# POWER_CONTROL.net
KiCad netlist of a schematic drawn in Altium Designer
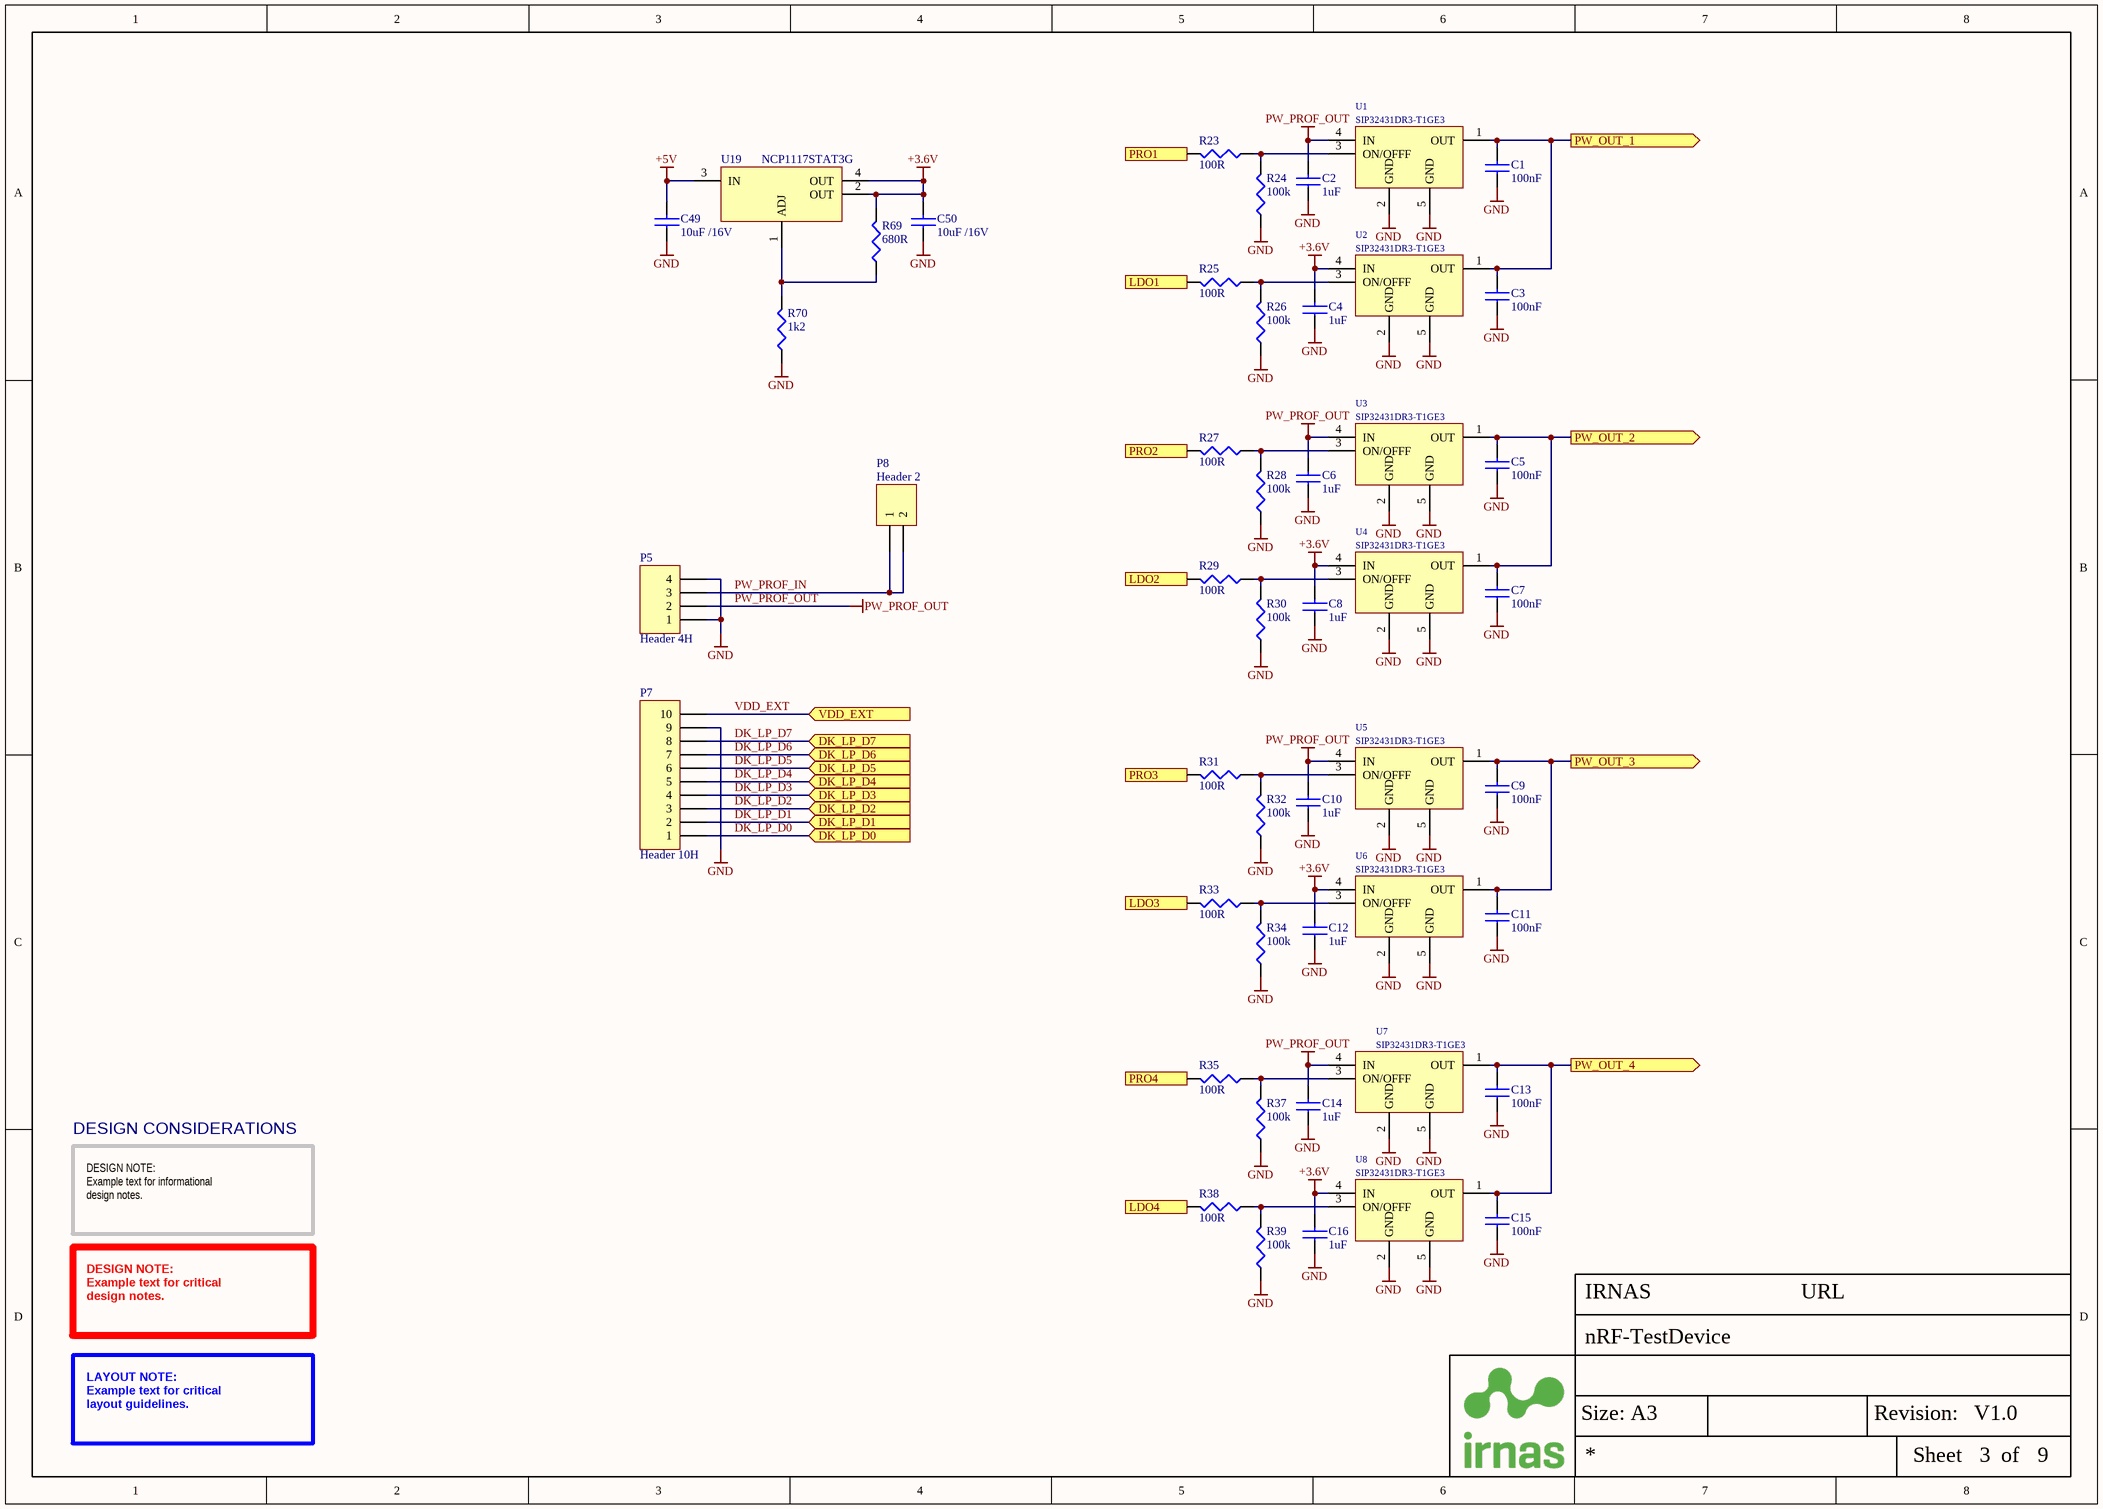
[diagram p0: POWER_CONTROL.SchDoc]

(export (version "E")
  (design (tool "Eeschema 10.0.6"))
  (components
    (comp (ref "C1")
      (value "100nF")
      (footprint "CAP0402")
      (fields
        (field (name "MANUFACTURER") "Multicomp")
        (field (name "MANUFACTURER PART NUMBER") "MC0402X104J160CT")
        (field (name "TOLERANCE") "5%")
      )
      (libsource (lib "Passive") (part "C - 100nF/0402"))
    )
    (comp (ref "C2")
      (value "1uF")
      (footprint "CAP0402")
      (description "CAP CER 1UF 10V 20% X5R 0402")
      (fields
        (field (name "MANUFACTURER") "Murata")
        (field (name "MANUFACTURER PART NUMBER") "GRM155R61A105ME15D")
      )
      (libsource (lib "Passive") (part "C - 1uF/0402"))
    )
    (comp (ref "C3")
      (value "100nF")
      (footprint "CAP0402")
      (fields
        (field (name "MANUFACTURER") "Multicomp")
        (field (name "MANUFACTURER PART NUMBER") "MC0402X104J160CT")
        (field (name "TOLERANCE") "5%")
      )
      (libsource (lib "Passive") (part "C - 100nF/0402"))
    )
    (comp (ref "C4")
      (value "1uF")
      (footprint "CAP0402")
      (description "CAP CER 1UF 10V 20% X5R 0402")
      (fields
        (field (name "MANUFACTURER") "Murata")
        (field (name "MANUFACTURER PART NUMBER") "GRM155R61A105ME15D")
      )
      (libsource (lib "Passive") (part "C - 1uF/0402"))
    )
    (comp (ref "C5")
      (value "100nF")
      (footprint "CAP0402")
      (fields
        (field (name "MANUFACTURER") "Multicomp")
        (field (name "MANUFACTURER PART NUMBER") "MC0402X104J160CT")
        (field (name "TOLERANCE") "5%")
      )
      (libsource (lib "Passive") (part "C - 100nF/0402"))
    )
    (comp (ref "C6")
      (value "1uF")
      (footprint "CAP0402")
      (description "CAP CER 1UF 10V 20% X5R 0402")
      (fields
        (field (name "MANUFACTURER") "Murata")
        (field (name "MANUFACTURER PART NUMBER") "GRM155R61A105ME15D")
      )
      (libsource (lib "Passive") (part "C - 1uF/0402"))
    )
    (comp (ref "C7")
      (value "100nF")
      (footprint "CAP0402")
      (fields
        (field (name "MANUFACTURER") "Multicomp")
        (field (name "MANUFACTURER PART NUMBER") "MC0402X104J160CT")
        (field (name "TOLERANCE") "5%")
      )
      (libsource (lib "Passive") (part "C - 100nF/0402"))
    )
    (comp (ref "C8")
      (value "1uF")
      (footprint "CAP0402")
      (description "CAP CER 1UF 10V 20% X5R 0402")
      (fields
        (field (name "MANUFACTURER") "Murata")
        (field (name "MANUFACTURER PART NUMBER") "GRM155R61A105ME15D")
      )
      (libsource (lib "Passive") (part "C - 1uF/0402"))
    )
    (comp (ref "C9")
      (value "100nF")
      (footprint "CAP0402")
      (fields
        (field (name "MANUFACTURER") "Multicomp")
        (field (name "MANUFACTURER PART NUMBER") "MC0402X104J160CT")
        (field (name "TOLERANCE") "5%")
      )
      (libsource (lib "Passive") (part "C - 100nF/0402"))
    )
    (comp (ref "C10")
      (value "1uF")
      (footprint "CAP0402")
      (description "CAP CER 1UF 10V 20% X5R 0402")
      (fields
        (field (name "MANUFACTURER") "Murata")
        (field (name "MANUFACTURER PART NUMBER") "GRM155R61A105ME15D")
      )
      (libsource (lib "Passive") (part "C - 1uF/0402"))
    )
    (comp (ref "C11")
      (value "100nF")
      (footprint "CAP0402")
      (fields
        (field (name "MANUFACTURER") "Multicomp")
        (field (name "MANUFACTURER PART NUMBER") "MC0402X104J160CT")
        (field (name "TOLERANCE") "5%")
      )
      (libsource (lib "Passive") (part "C - 100nF/0402"))
    )
    (comp (ref "C12")
      (value "1uF")
      (footprint "CAP0402")
      (description "CAP CER 1UF 10V 20% X5R 0402")
      (fields
        (field (name "MANUFACTURER") "Murata")
        (field (name "MANUFACTURER PART NUMBER") "GRM155R61A105ME15D")
      )
      (libsource (lib "Passive") (part "C - 1uF/0402"))
    )
    (comp (ref "C13")
      (value "100nF")
      (footprint "CAP0402")
      (fields
        (field (name "MANUFACTURER") "Multicomp")
        (field (name "MANUFACTURER PART NUMBER") "MC0402X104J160CT")
        (field (name "TOLERANCE") "5%")
      )
      (libsource (lib "Passive") (part "C - 100nF/0402"))
    )
    (comp (ref "C14")
      (value "1uF")
      (footprint "CAP0402")
      (description "CAP CER 1UF 10V 20% X5R 0402")
      (fields
        (field (name "MANUFACTURER") "Murata")
        (field (name "MANUFACTURER PART NUMBER") "GRM155R61A105ME15D")
      )
      (libsource (lib "Passive") (part "C - 1uF/0402"))
    )
    (comp (ref "C15")
      (value "100nF")
      (footprint "CAP0402")
      (fields
        (field (name "MANUFACTURER") "Multicomp")
        (field (name "MANUFACTURER PART NUMBER") "MC0402X104J160CT")
        (field (name "TOLERANCE") "5%")
      )
      (libsource (lib "Passive") (part "C - 100nF/0402"))
    )
    (comp (ref "C16")
      (value "1uF")
      (footprint "CAP0402")
      (description "CAP CER 1UF 10V 20% X5R 0402")
      (fields
        (field (name "MANUFACTURER") "Murata")
        (field (name "MANUFACTURER PART NUMBER") "GRM155R61A105ME15D")
      )
      (libsource (lib "Passive") (part "C - 1uF/0402"))
    )
    (comp (ref "C49")
      (value "10uF /16V")
      (footprint "CAP0805")
      (description "TDK - CGA4J1X5R1C106K125AC - CAP, MLCC, X5R, 10UF, 16V, 0805")
      (fields
        (field (name "MANUFACTURER") "TDK")
        (field (name "MANUFACTURER PART NUMBER") "CGA4J1X5R1C106K125AC")
      )
      (libsource (lib "Passive") (part "C - 10uF /16V"))
    )
    (comp (ref "C50")
      (value "10uF /16V")
      (footprint "CAP0805")
      (description "TDK - CGA4J1X5R1C106K125AC - CAP, MLCC, X5R, 10UF, 16V, 0805")
      (fields
        (field (name "MANUFACTURER") "TDK")
        (field (name "MANUFACTURER PART NUMBER") "CGA4J1X5R1C106K125AC")
      )
      (libsource (lib "Passive") (part "C - 10uF /16V"))
    )
    (comp (ref "P5")
      (value "Header 4H")
      (footprint "HDR1X4H")
      (description "Header, 4-Pin, Right Angle")
      (fields (field (name "PUBLISHER") "Altium Limited"))
      (libsource (lib "Miscellaneous Connectors") (part "Header 4H"))
    )
    (comp (ref "P7")
      (value "Header 10H")
      (footprint "HDR1X10H")
      (description "Header, 10-Pin, Right Angle")
      (fields (field (name "PUBLISHER") "Altium Limited"))
      (libsource (lib "Miscellaneous Connectors") (part "Header 10H"))
    )
    (comp (ref "P8")
      (value "Header 2")
      (footprint "HDR1X2")
      (description "Header, 2-Pin")
      (fields (field (name "PUBLISHER") "Altium Limited"))
      (libsource (lib "Miscellaneous Connectors") (part "Header 2"))
    )
    (comp (ref "R23")
      (value "100R")
      (footprint "RES0402")
      (fields
        (field (name "MANUFACTURER") "Multicomp")
        (field (name "MANUFACTURER PART NUMBER") "MCMR04X1000FTL")
        (field (name "TOLERANCE") "1%")
      )
      (libsource (lib "Passive") (part "R - 100R/0402"))
    )
    (comp (ref "R24")
      (value "100k")
      (footprint "RES0402")
      (description "MULTICOMP   MCWR04X1003FTL   RES, THICK FILM, 100KOHM, 1%, 0.0625W")
      (fields
        (field (name "MANUFACTURER") "Multicomp")
        (field (name "MANUFACTURER PART NUMBER") "MCWR04X1003FTL")
      )
      (libsource (lib "Passive") (part "R - 100k/0402"))
    )
    (comp (ref "R25")
      (value "100R")
      (footprint "RES0402")
      (fields
        (field (name "MANUFACTURER") "Multicomp")
        (field (name "MANUFACTURER PART NUMBER") "MCMR04X1000FTL")
        (field (name "TOLERANCE") "1%")
      )
      (libsource (lib "Passive") (part "R - 100R/0402"))
    )
    (comp (ref "R26")
      (value "100k")
      (footprint "RES0402")
      (description "MULTICOMP   MCWR04X1003FTL   RES, THICK FILM, 100KOHM, 1%, 0.0625W")
      (fields
        (field (name "MANUFACTURER") "Multicomp")
        (field (name "MANUFACTURER PART NUMBER") "MCWR04X1003FTL")
      )
      (libsource (lib "Passive") (part "R - 100k/0402"))
    )
    (comp (ref "R27")
      (value "100R")
      (footprint "RES0402")
      (fields
        (field (name "MANUFACTURER") "Multicomp")
        (field (name "MANUFACTURER PART NUMBER") "MCMR04X1000FTL")
        (field (name "TOLERANCE") "1%")
      )
      (libsource (lib "Passive") (part "R - 100R/0402"))
    )
    (comp (ref "R28")
      (value "100k")
      (footprint "RES0402")
      (description "MULTICOMP   MCWR04X1003FTL   RES, THICK FILM, 100KOHM, 1%, 0.0625W")
      (fields
        (field (name "MANUFACTURER") "Multicomp")
        (field (name "MANUFACTURER PART NUMBER") "MCWR04X1003FTL")
      )
      (libsource (lib "Passive") (part "R - 100k/0402"))
    )
    (comp (ref "R29")
      (value "100R")
      (footprint "RES0402")
      (fields
        (field (name "MANUFACTURER") "Multicomp")
        (field (name "MANUFACTURER PART NUMBER") "MCMR04X1000FTL")
        (field (name "TOLERANCE") "1%")
      )
      (libsource (lib "Passive") (part "R - 100R/0402"))
    )
    (comp (ref "R30")
      (value "100k")
      (footprint "RES0402")
      (description "MULTICOMP   MCWR04X1003FTL   RES, THICK FILM, 100KOHM, 1%, 0.0625W")
      (fields
        (field (name "MANUFACTURER") "Multicomp")
        (field (name "MANUFACTURER PART NUMBER") "MCWR04X1003FTL")
      )
      (libsource (lib "Passive") (part "R - 100k/0402"))
    )
    (comp (ref "R31")
      (value "100R")
      (footprint "RES0402")
      (fields
        (field (name "MANUFACTURER") "Multicomp")
        (field (name "MANUFACTURER PART NUMBER") "MCMR04X1000FTL")
        (field (name "TOLERANCE") "1%")
      )
      (libsource (lib "Passive") (part "R - 100R/0402"))
    )
    (comp (ref "R32")
      (value "100k")
      (footprint "RES0402")
      (description "MULTICOMP   MCWR04X1003FTL   RES, THICK FILM, 100KOHM, 1%, 0.0625W")
      (fields
        (field (name "MANUFACTURER") "Multicomp")
        (field (name "MANUFACTURER PART NUMBER") "MCWR04X1003FTL")
      )
      (libsource (lib "Passive") (part "R - 100k/0402"))
    )
    (comp (ref "R33")
      (value "100R")
      (footprint "RES0402")
      (fields
        (field (name "MANUFACTURER") "Multicomp")
        (field (name "MANUFACTURER PART NUMBER") "MCMR04X1000FTL")
        (field (name "TOLERANCE") "1%")
      )
      (libsource (lib "Passive") (part "R - 100R/0402"))
    )
    (comp (ref "R34")
      (value "100k")
      (footprint "RES0402")
      (description "MULTICOMP   MCWR04X1003FTL   RES, THICK FILM, 100KOHM, 1%, 0.0625W")
      (fields
        (field (name "MANUFACTURER") "Multicomp")
        (field (name "MANUFACTURER PART NUMBER") "MCWR04X1003FTL")
      )
      (libsource (lib "Passive") (part "R - 100k/0402"))
    )
    (comp (ref "R35")
      (value "100R")
      (footprint "RES0402")
      (fields
        (field (name "MANUFACTURER") "Multicomp")
        (field (name "MANUFACTURER PART NUMBER") "MCMR04X1000FTL")
        (field (name "TOLERANCE") "1%")
      )
      (libsource (lib "Passive") (part "R - 100R/0402"))
    )
    (comp (ref "R37")
      (value "100k")
      (footprint "RES0402")
      (description "MULTICOMP   MCWR04X1003FTL   RES, THICK FILM, 100KOHM, 1%, 0.0625W")
      (fields
        (field (name "MANUFACTURER") "Multicomp")
        (field (name "MANUFACTURER PART NUMBER") "MCWR04X1003FTL")
      )
      (libsource (lib "Passive") (part "R - 100k/0402"))
    )
    (comp (ref "R38")
      (value "100R")
      (footprint "RES0402")
      (fields
        (field (name "MANUFACTURER") "Multicomp")
        (field (name "MANUFACTURER PART NUMBER") "MCMR04X1000FTL")
        (field (name "TOLERANCE") "1%")
      )
      (libsource (lib "Passive") (part "R - 100R/0402"))
    )
    (comp (ref "R39")
      (value "100k")
      (footprint "RES0402")
      (description "MULTICOMP   MCWR04X1003FTL   RES, THICK FILM, 100KOHM, 1%, 0.0625W")
      (fields
        (field (name "MANUFACTURER") "Multicomp")
        (field (name "MANUFACTURER PART NUMBER") "MCWR04X1003FTL")
      )
      (libsource (lib "Passive") (part "R - 100k/0402"))
    )
    (comp (ref "R69")
      (value "680R")
      (footprint "RES0402")
      (description "RES 680 ohm, ± 1%, 63 mW, 0402")
      (fields
        (field (name "MANUFACTURER") "Vishay")
        (field (name "MANUFACTURER PART NUMBER") "CRCW0402680RFKED")
      )
      (libsource (lib "Passive") (part "R - 680R/0402"))
    )
    (comp (ref "R70")
      (value "1k2")
      (footprint "RES0402")
      (description "RES SMD 1.2K OHM 1% 1/16W 0402")
      (fields
        (field (name "MANUFACTURER") "Vishay")
        (field (name "MANUFACTURER PART NUMBER") "CRCW04021K20FKED")
      )
      (libsource (lib "Passive") (part "R - 1k2/0402"))
    )
    (comp (ref "U1")
      (value "SIP32431DR3-T1GE3")
      (footprint "SC70-6")
      (description "Power Load Switch, Reverse Blocking, High Side, Active High, Active Low, 1 Output, 5.5V, 1A")
      (libsource (lib "Active") (part "SW - SIP32431DR3-T1GE3"))
    )
    (comp (ref "U2")
      (value "SIP32431DR3-T1GE3")
      (footprint "SC70-6")
      (description "Power Load Switch, Reverse Blocking, High Side, Active High, Active Low, 1 Output, 5.5V, 1A")
      (libsource (lib "Active") (part "SW - SIP32431DR3-T1GE3"))
    )
    (comp (ref "U3")
      (value "SIP32431DR3-T1GE3")
      (footprint "SC70-6")
      (description "Power Load Switch, Reverse Blocking, High Side, Active High, Active Low, 1 Output, 5.5V, 1A")
      (libsource (lib "Active") (part "SW - SIP32431DR3-T1GE3"))
    )
    (comp (ref "U4")
      (value "SIP32431DR3-T1GE3")
      (footprint "SC70-6")
      (description "Power Load Switch, Reverse Blocking, High Side, Active High, Active Low, 1 Output, 5.5V, 1A")
      (libsource (lib "Active") (part "SW - SIP32431DR3-T1GE3"))
    )
    (comp (ref "U5")
      (value "SIP32431DR3-T1GE3")
      (footprint "SC70-6")
      (description "Power Load Switch, Reverse Blocking, High Side, Active High, Active Low, 1 Output, 5.5V, 1A")
      (libsource (lib "Active") (part "SW - SIP32431DR3-T1GE3"))
    )
    (comp (ref "U6")
      (value "SIP32431DR3-T1GE3")
      (footprint "SC70-6")
      (description "Power Load Switch, Reverse Blocking, High Side, Active High, Active Low, 1 Output, 5.5V, 1A")
      (libsource (lib "Active") (part "SW - SIP32431DR3-T1GE3"))
    )
    (comp (ref "U7")
      (value "SIP32431DR3-T1GE3")
      (footprint "SC70-6")
      (description "Power Load Switch, Reverse Blocking, High Side, Active High, Active Low, 1 Output, 5.5V, 1A")
      (libsource (lib "Active") (part "SW - SIP32431DR3-T1GE3"))
    )
    (comp (ref "U8")
      (value "SIP32431DR3-T1GE3")
      (footprint "SC70-6")
      (description "Power Load Switch, Reverse Blocking, High Side, Active High, Active Low, 1 Output, 5.5V, 1A")
      (libsource (lib "Active") (part "SW - SIP32431DR3-T1GE3"))
    )
    (comp (ref "U19")
      (value "NCP1117STAT3G")
      (footprint "SOT223-3")
      (description "LDO Voltage Regulator, Adjustable, 3.5V to 20V in, 1.07V drop, 1.25V to 18.8V/1A out, SOT-223-3")
      (fields (field (name "MANUFACTURER") "ON SEMICONDUCTOR"))
      (libsource (lib "Active") (part "V_LIN - NCP1117STAT3G"))
    )
  )
  (nets
    (net (code "1") (name "+3.6V") (class "Default")
      (node (ref "C12") (pin "2") (pinfunction "2_2") (pintype "passive"))
      (node (ref "C16") (pin "2") (pinfunction "2_2") (pintype "passive"))
      (node (ref "C4") (pin "2") (pinfunction "2_2") (pintype "passive"))
      (node (ref "C50") (pin "2") (pinfunction "2_2") (pintype "passive"))
      (node (ref "C8") (pin "2") (pinfunction "2_2") (pintype "passive"))
      (node (ref "R69") (pin "2") (pinfunction "2_2") (pintype "passive"))
      (node (ref "U19") (pin "2") (pinfunction "OUT_2") (pintype "open_collector"))
      (node (ref "U19") (pin "4") (pinfunction "OUT_4") (pintype "open_collector"))
      (node (ref "U2") (pin "4") (pinfunction "IN_4") (pintype "passive"))
      (node (ref "U4") (pin "4") (pinfunction "IN_4") (pintype "passive"))
      (node (ref "U6") (pin "4") (pinfunction "IN_4") (pintype "passive"))
      (node (ref "U8") (pin "4") (pinfunction "IN_4") (pintype "passive"))
    )
    (net (code "2") (name "+5V") (class "Default")
      (node (ref "C49") (pin "2") (pinfunction "2_2") (pintype "passive"))
      (node (ref "U19") (pin "3") (pinfunction "IN_3") (pintype "open_collector"))
    )
    (net (code "3") (name "/DK_LP_D0") (class "Default")
      (node (ref "P7") (pin "1") (pinfunction "1_1") (pintype "passive"))
    )
    (net (code "4") (name "/DK_LP_D1") (class "Default")
      (node (ref "P7") (pin "2") (pinfunction "2_2") (pintype "passive"))
    )
    (net (code "5") (name "/DK_LP_D2") (class "Default")
      (node (ref "P7") (pin "3") (pinfunction "3_3") (pintype "passive"))
    )
    (net (code "6") (name "/DK_LP_D3") (class "Default")
      (node (ref "P7") (pin "4") (pinfunction "4_4") (pintype "passive"))
    )
    (net (code "7") (name "/DK_LP_D4") (class "Default")
      (node (ref "P7") (pin "5") (pinfunction "5_5") (pintype "passive"))
    )
    (net (code "8") (name "/DK_LP_D5") (class "Default")
      (node (ref "P7") (pin "6") (pinfunction "6_6") (pintype "passive"))
    )
    (net (code "9") (name "/DK_LP_D6") (class "Default")
      (node (ref "P7") (pin "7") (pinfunction "7_7") (pintype "passive"))
    )
    (net (code "10") (name "/DK_LP_D7") (class "Default")
      (node (ref "P7") (pin "8") (pinfunction "8_8") (pintype "passive"))
    )
    (net (code "11") (name "/LDO1") (class "Default")
      (node (ref "R25") (pin "2") (pinfunction "2_2") (pintype "passive"))
    )
    (net (code "12") (name "/LDO2") (class "Default")
      (node (ref "R29") (pin "2") (pinfunction "2_2") (pintype "passive"))
    )
    (net (code "13") (name "/LDO3") (class "Default")
      (node (ref "R33") (pin "2") (pinfunction "2_2") (pintype "passive"))
    )
    (net (code "14") (name "/LDO4") (class "Default")
      (node (ref "R38") (pin "2") (pinfunction "2_2") (pintype "passive"))
    )
    (net (code "15") (name "/PRO1") (class "Default")
      (node (ref "R23") (pin "2") (pinfunction "2_2") (pintype "passive"))
    )
    (net (code "16") (name "/PRO2") (class "Default")
      (node (ref "R27") (pin "2") (pinfunction "2_2") (pintype "passive"))
    )
    (net (code "17") (name "/PRO3") (class "Default")
      (node (ref "R31") (pin "2") (pinfunction "2_2") (pintype "passive"))
    )
    (net (code "18") (name "/PRO4") (class "Default")
      (node (ref "R35") (pin "2") (pinfunction "2_2") (pintype "passive"))
    )
    (net (code "19") (name "/PW_OUT_1") (class "Default")
      (node (ref "C1") (pin "2") (pinfunction "2_2") (pintype "passive"))
      (node (ref "C3") (pin "2") (pinfunction "2_2") (pintype "passive"))
      (node (ref "U1") (pin "1") (pinfunction "OUT_1") (pintype "passive"))
      (node (ref "U2") (pin "1") (pinfunction "OUT_1") (pintype "passive"))
    )
    (net (code "20") (name "/PW_OUT_2") (class "Default")
      (node (ref "C5") (pin "2") (pinfunction "2_2") (pintype "passive"))
      (node (ref "C7") (pin "2") (pinfunction "2_2") (pintype "passive"))
      (node (ref "U3") (pin "1") (pinfunction "OUT_1") (pintype "passive"))
      (node (ref "U4") (pin "1") (pinfunction "OUT_1") (pintype "passive"))
    )
    (net (code "21") (name "/PW_OUT_3") (class "Default")
      (node (ref "C11") (pin "2") (pinfunction "2_2") (pintype "passive"))
      (node (ref "C9") (pin "2") (pinfunction "2_2") (pintype "passive"))
      (node (ref "U5") (pin "1") (pinfunction "OUT_1") (pintype "passive"))
      (node (ref "U6") (pin "1") (pinfunction "OUT_1") (pintype "passive"))
    )
    (net (code "22") (name "/PW_OUT_4") (class "Default")
      (node (ref "C13") (pin "2") (pinfunction "2_2") (pintype "passive"))
      (node (ref "C15") (pin "2") (pinfunction "2_2") (pintype "passive"))
      (node (ref "U7") (pin "1") (pinfunction "OUT_1") (pintype "passive"))
      (node (ref "U8") (pin "1") (pinfunction "OUT_1") (pintype "passive"))
    )
    (net (code "23") (name "/PW_PROF_IN") (class "Default")
      (node (ref "P5") (pin "3") (pinfunction "3_3") (pintype "passive"))
      (node (ref "P8") (pin "1") (pinfunction "1_1") (pintype "passive"))
      (node (ref "P8") (pin "2") (pinfunction "2_2") (pintype "passive"))
    )
    (net (code "24") (name "/VDD_EXT") (class "Default")
      (node (ref "P7") (pin "10") (pinfunction "10_10") (pintype "passive"))
    )
    (net (code "25") (name "GND") (class "Default")
      (node (ref "C1") (pin "1") (pinfunction "1_1") (pintype "passive"))
      (node (ref "C10") (pin "1") (pinfunction "1_1") (pintype "passive"))
      (node (ref "C11") (pin "1") (pinfunction "1_1") (pintype "passive"))
      (node (ref "C12") (pin "1") (pinfunction "1_1") (pintype "passive"))
      (node (ref "C13") (pin "1") (pinfunction "1_1") (pintype "passive"))
      (node (ref "C14") (pin "1") (pinfunction "1_1") (pintype "passive"))
      (node (ref "C15") (pin "1") (pinfunction "1_1") (pintype "passive"))
      (node (ref "C16") (pin "1") (pinfunction "1_1") (pintype "passive"))
      (node (ref "C2") (pin "1") (pinfunction "1_1") (pintype "passive"))
      (node (ref "C3") (pin "1") (pinfunction "1_1") (pintype "passive"))
      (node (ref "C4") (pin "1") (pinfunction "1_1") (pintype "passive"))
      (node (ref "C49") (pin "1") (pinfunction "1_1") (pintype "passive"))
      (node (ref "C5") (pin "1") (pinfunction "1_1") (pintype "passive"))
      (node (ref "C50") (pin "1") (pinfunction "1_1") (pintype "passive"))
      (node (ref "C6") (pin "1") (pinfunction "1_1") (pintype "passive"))
      (node (ref "C7") (pin "1") (pinfunction "1_1") (pintype "passive"))
      (node (ref "C8") (pin "1") (pinfunction "1_1") (pintype "passive"))
      (node (ref "C9") (pin "1") (pinfunction "1_1") (pintype "passive"))
      (node (ref "P5") (pin "1") (pinfunction "1_1") (pintype "passive"))
      (node (ref "P5") (pin "4") (pinfunction "4_4") (pintype "passive"))
      (node (ref "P7") (pin "9") (pinfunction "9_9") (pintype "passive"))
      (node (ref "R24") (pin "1") (pinfunction "1_1") (pintype "passive"))
      (node (ref "R26") (pin "1") (pinfunction "1_1") (pintype "passive"))
      (node (ref "R28") (pin "1") (pinfunction "1_1") (pintype "passive"))
      (node (ref "R30") (pin "1") (pinfunction "1_1") (pintype "passive"))
      (node (ref "R32") (pin "1") (pinfunction "1_1") (pintype "passive"))
      (node (ref "R34") (pin "1") (pinfunction "1_1") (pintype "passive"))
      (node (ref "R37") (pin "1") (pinfunction "1_1") (pintype "passive"))
      (node (ref "R39") (pin "1") (pinfunction "1_1") (pintype "passive"))
      (node (ref "R70") (pin "1") (pinfunction "1_1") (pintype "passive"))
      (node (ref "U1") (pin "2") (pinfunction "GND_2") (pintype "passive"))
      (node (ref "U1") (pin "5") (pinfunction "GND_5") (pintype "passive"))
      (node (ref "U2") (pin "2") (pinfunction "GND_2") (pintype "passive"))
      (node (ref "U2") (pin "5") (pinfunction "GND_5") (pintype "passive"))
      (node (ref "U3") (pin "2") (pinfunction "GND_2") (pintype "passive"))
      (node (ref "U3") (pin "5") (pinfunction "GND_5") (pintype "passive"))
      (node (ref "U4") (pin "2") (pinfunction "GND_2") (pintype "passive"))
      (node (ref "U4") (pin "5") (pinfunction "GND_5") (pintype "passive"))
      (node (ref "U5") (pin "2") (pinfunction "GND_2") (pintype "passive"))
      (node (ref "U5") (pin "5") (pinfunction "GND_5") (pintype "passive"))
      (node (ref "U6") (pin "2") (pinfunction "GND_2") (pintype "passive"))
      (node (ref "U6") (pin "5") (pinfunction "GND_5") (pintype "passive"))
      (node (ref "U7") (pin "2") (pinfunction "GND_2") (pintype "passive"))
      (node (ref "U7") (pin "5") (pinfunction "GND_5") (pintype "passive"))
      (node (ref "U8") (pin "2") (pinfunction "GND_2") (pintype "passive"))
      (node (ref "U8") (pin "5") (pinfunction "GND_5") (pintype "passive"))
    )
    (net (code "26") (name "Net-(U1-ON{slash}OFFF)") (class "Default")
      (node (ref "R23") (pin "1") (pinfunction "1_1") (pintype "passive"))
      (node (ref "R24") (pin "2") (pinfunction "2_2") (pintype "passive"))
      (node (ref "U1") (pin "3") (pinfunction "ON/OFFF_3") (pintype "passive"))
    )
    (net (code "27") (name "Net-(U2-ON{slash}OFFF)") (class "Default")
      (node (ref "R25") (pin "1") (pinfunction "1_1") (pintype "passive"))
      (node (ref "R26") (pin "2") (pinfunction "2_2") (pintype "passive"))
      (node (ref "U2") (pin "3") (pinfunction "ON/OFFF_3") (pintype "passive"))
    )
    (net (code "28") (name "Net-(U3-ON{slash}OFFF)") (class "Default")
      (node (ref "R27") (pin "1") (pinfunction "1_1") (pintype "passive"))
      (node (ref "R28") (pin "2") (pinfunction "2_2") (pintype "passive"))
      (node (ref "U3") (pin "3") (pinfunction "ON/OFFF_3") (pintype "passive"))
    )
    (net (code "29") (name "Net-(U4-ON{slash}OFFF)") (class "Default")
      (node (ref "R29") (pin "1") (pinfunction "1_1") (pintype "passive"))
      (node (ref "R30") (pin "2") (pinfunction "2_2") (pintype "passive"))
      (node (ref "U4") (pin "3") (pinfunction "ON/OFFF_3") (pintype "passive"))
    )
    (net (code "30") (name "Net-(U5-ON{slash}OFFF)") (class "Default")
      (node (ref "R31") (pin "1") (pinfunction "1_1") (pintype "passive"))
      (node (ref "R32") (pin "2") (pinfunction "2_2") (pintype "passive"))
      (node (ref "U5") (pin "3") (pinfunction "ON/OFFF_3") (pintype "passive"))
    )
    (net (code "31") (name "Net-(U6-ON{slash}OFFF)") (class "Default")
      (node (ref "R33") (pin "1") (pinfunction "1_1") (pintype "passive"))
      (node (ref "R34") (pin "2") (pinfunction "2_2") (pintype "passive"))
      (node (ref "U6") (pin "3") (pinfunction "ON/OFFF_3") (pintype "passive"))
    )
    (net (code "32") (name "Net-(U7-ON{slash}OFFF)") (class "Default")
      (node (ref "R35") (pin "1") (pinfunction "1_1") (pintype "passive"))
      (node (ref "R37") (pin "2") (pinfunction "2_2") (pintype "passive"))
      (node (ref "U7") (pin "3") (pinfunction "ON/OFFF_3") (pintype "passive"))
    )
    (net (code "33") (name "Net-(U8-ON{slash}OFFF)") (class "Default")
      (node (ref "R38") (pin "1") (pinfunction "1_1") (pintype "passive"))
      (node (ref "R39") (pin "2") (pinfunction "2_2") (pintype "passive"))
      (node (ref "U8") (pin "3") (pinfunction "ON/OFFF_3") (pintype "passive"))
    )
    (net (code "34") (name "Net-(U19-ADJ)") (class "Default")
      (node (ref "R69") (pin "1") (pinfunction "1_1") (pintype "passive"))
      (node (ref "R70") (pin "2") (pinfunction "2_2") (pintype "passive"))
      (node (ref "U19") (pin "1") (pinfunction "ADJ_1") (pintype "open_collector"))
    )
    (net (code "35") (name "PW_PROF_OUT") (class "Default")
      (node (ref "C10") (pin "2") (pinfunction "2_2") (pintype "passive"))
      (node (ref "C14") (pin "2") (pinfunction "2_2") (pintype "passive"))
      (node (ref "C2") (pin "2") (pinfunction "2_2") (pintype "passive"))
      (node (ref "C6") (pin "2") (pinfunction "2_2") (pintype "passive"))
      (node (ref "P5") (pin "2") (pinfunction "2_2") (pintype "passive"))
      (node (ref "U1") (pin "4") (pinfunction "IN_4") (pintype "passive"))
      (node (ref "U3") (pin "4") (pinfunction "IN_4") (pintype "passive"))
      (node (ref "U5") (pin "4") (pinfunction "IN_4") (pintype "passive"))
      (node (ref "U7") (pin "4") (pinfunction "IN_4") (pintype "passive"))
    )
  )
)
